# riffle-proto-0_1.net
KiCad netlist of a schematic drawn in EAGLE
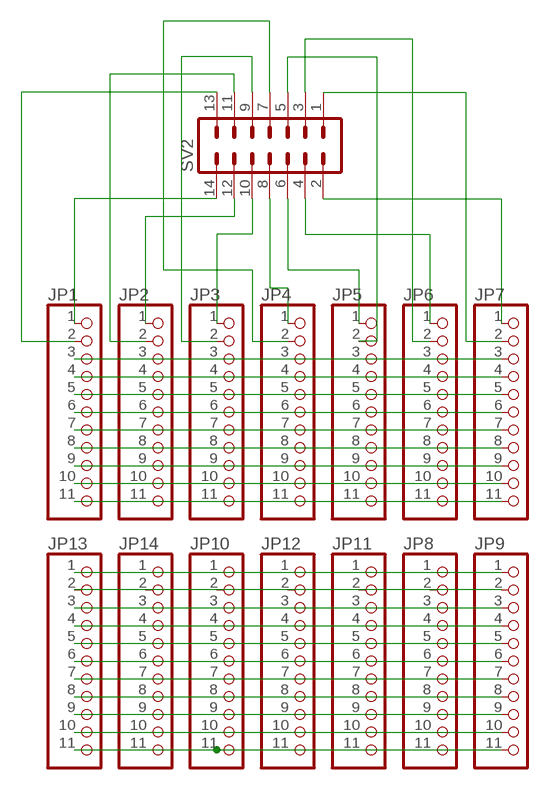
[diagram p0: schematic, sheet 1]

(export (version "E")
  (design (tool "Eeschema 10.0.6"))
  (components
    (comp (ref "JP1")
      (value "HEADER-1X1176MIL")
      (footprint "eagle-import:1X11_ROUND_76")
      (libsource (lib "eagle-import") (part "HEADER-1X1176MIL"))
    )
    (comp (ref "JP2")
      (value "HEADER-1X1176MIL")
      (footprint "eagle-import:1X11_ROUND_76")
      (libsource (lib "eagle-import") (part "HEADER-1X1176MIL"))
    )
    (comp (ref "JP3")
      (value "HEADER-1X1176MIL")
      (footprint "eagle-import:1X11_ROUND_76")
      (libsource (lib "eagle-import") (part "HEADER-1X1176MIL"))
    )
    (comp (ref "JP4")
      (value "HEADER-1X1176MIL")
      (footprint "eagle-import:1X11_ROUND_76")
      (libsource (lib "eagle-import") (part "HEADER-1X1176MIL"))
    )
    (comp (ref "JP5")
      (value "HEADER-1X1176MIL")
      (footprint "eagle-import:1X11_ROUND_76")
      (libsource (lib "eagle-import") (part "HEADER-1X1176MIL"))
    )
    (comp (ref "JP6")
      (value "HEADER-1X1176MIL")
      (footprint "eagle-import:1X11_ROUND_76")
      (libsource (lib "eagle-import") (part "HEADER-1X1176MIL"))
    )
    (comp (ref "JP7")
      (value "HEADER-1X1176MIL")
      (footprint "eagle-import:1X11_ROUND_76")
      (libsource (lib "eagle-import") (part "HEADER-1X1176MIL"))
    )
    (comp (ref "JP8")
      (value "HEADER-1X1176MIL")
      (footprint "eagle-import:1X11_ROUND_76")
      (libsource (lib "eagle-import") (part "HEADER-1X1176MIL"))
    )
    (comp (ref "JP9")
      (value "HEADER-1X1176MIL")
      (footprint "eagle-import:1X11_ROUND_76")
      (libsource (lib "eagle-import") (part "HEADER-1X1176MIL"))
    )
    (comp (ref "JP10")
      (value "HEADER-1X1176MIL")
      (footprint "eagle-import:1X11_ROUND_76")
      (libsource (lib "eagle-import") (part "HEADER-1X1176MIL"))
    )
    (comp (ref "JP11")
      (value "HEADER-1X1176MIL")
      (footprint "eagle-import:1X11_ROUND_76")
      (libsource (lib "eagle-import") (part "HEADER-1X1176MIL"))
    )
    (comp (ref "JP12")
      (value "HEADER-1X1176MIL")
      (footprint "eagle-import:1X11_ROUND_76")
      (libsource (lib "eagle-import") (part "HEADER-1X1176MIL"))
    )
    (comp (ref "JP13")
      (value "HEADER-1X1176MIL")
      (footprint "eagle-import:1X11_ROUND_76")
      (libsource (lib "eagle-import") (part "HEADER-1X1176MIL"))
    )
    (comp (ref "JP14")
      (value "HEADER-1X1176MIL")
      (footprint "eagle-import:1X11_ROUND_76")
      (libsource (lib "eagle-import") (part "HEADER-1X1176MIL"))
    )
    (comp (ref "SV2")
      (value "MA07-2")
      (footprint "eagle-import:MA07-2")
      (libsource (lib "eagle-import") (part "MA07-2"))
    )
  )
  (nets
    (net (code "1") (name "Net-(JP1-Pad1)") (class "Default")
      (node (ref "JP1") (pin "1") (pinfunction "1_1") (pintype "passive"))
      (node (ref "SV2") (pin "14") (pinfunction "14_14") (pintype "passive"))
    )
    (net (code "2") (name "Net-(JP1-Pad2)") (class "Default")
      (node (ref "JP1") (pin "2") (pinfunction "2_2") (pintype "passive"))
      (node (ref "SV2") (pin "13") (pinfunction "13_13") (pintype "passive"))
    )
    (net (code "3") (name "Net-(JP1-Pad3)") (class "Default")
      (node (ref "JP1") (pin "3") (pinfunction "3_3") (pintype "passive"))
      (node (ref "JP2") (pin "3") (pinfunction "3_3") (pintype "passive"))
      (node (ref "JP3") (pin "3") (pinfunction "3_3") (pintype "passive"))
      (node (ref "JP4") (pin "3") (pinfunction "3_3") (pintype "passive"))
      (node (ref "JP5") (pin "3") (pinfunction "3_3") (pintype "passive"))
      (node (ref "JP6") (pin "3") (pinfunction "3_3") (pintype "passive"))
      (node (ref "JP7") (pin "3") (pinfunction "3_3") (pintype "passive"))
    )
    (net (code "4") (name "Net-(JP1-Pad4)") (class "Default")
      (node (ref "JP1") (pin "4") (pinfunction "4_4") (pintype "passive"))
      (node (ref "JP2") (pin "4") (pinfunction "4_4") (pintype "passive"))
      (node (ref "JP3") (pin "4") (pinfunction "4_4") (pintype "passive"))
      (node (ref "JP4") (pin "4") (pinfunction "4_4") (pintype "passive"))
      (node (ref "JP5") (pin "4") (pinfunction "4_4") (pintype "passive"))
      (node (ref "JP6") (pin "4") (pinfunction "4_4") (pintype "passive"))
      (node (ref "JP7") (pin "4") (pinfunction "4_4") (pintype "passive"))
    )
    (net (code "5") (name "Net-(JP1-Pad5)") (class "Default")
      (node (ref "JP1") (pin "5") (pinfunction "5_5") (pintype "passive"))
      (node (ref "JP2") (pin "5") (pinfunction "5_5") (pintype "passive"))
      (node (ref "JP3") (pin "5") (pinfunction "5_5") (pintype "passive"))
      (node (ref "JP4") (pin "5") (pinfunction "5_5") (pintype "passive"))
      (node (ref "JP5") (pin "5") (pinfunction "5_5") (pintype "passive"))
      (node (ref "JP6") (pin "5") (pinfunction "5_5") (pintype "passive"))
      (node (ref "JP7") (pin "5") (pinfunction "5_5") (pintype "passive"))
    )
    (net (code "6") (name "Net-(JP1-Pad6)") (class "Default")
      (node (ref "JP1") (pin "6") (pinfunction "6_6") (pintype "passive"))
      (node (ref "JP2") (pin "6") (pinfunction "6_6") (pintype "passive"))
      (node (ref "JP3") (pin "6") (pinfunction "6_6") (pintype "passive"))
      (node (ref "JP4") (pin "6") (pinfunction "6_6") (pintype "passive"))
      (node (ref "JP5") (pin "6") (pinfunction "6_6") (pintype "passive"))
      (node (ref "JP6") (pin "6") (pinfunction "6_6") (pintype "passive"))
      (node (ref "JP7") (pin "6") (pinfunction "6_6") (pintype "passive"))
    )
    (net (code "7") (name "Net-(JP1-Pad7)") (class "Default")
      (node (ref "JP1") (pin "7") (pinfunction "7_7") (pintype "passive"))
      (node (ref "JP2") (pin "7") (pinfunction "7_7") (pintype "passive"))
      (node (ref "JP3") (pin "7") (pinfunction "7_7") (pintype "passive"))
      (node (ref "JP4") (pin "7") (pinfunction "7_7") (pintype "passive"))
      (node (ref "JP5") (pin "7") (pinfunction "7_7") (pintype "passive"))
      (node (ref "JP6") (pin "7") (pinfunction "7_7") (pintype "passive"))
      (node (ref "JP7") (pin "7") (pinfunction "7_7") (pintype "passive"))
    )
    (net (code "8") (name "Net-(JP1-Pad8)") (class "Default")
      (node (ref "JP1") (pin "8") (pinfunction "8_8") (pintype "passive"))
      (node (ref "JP2") (pin "8") (pinfunction "8_8") (pintype "passive"))
      (node (ref "JP3") (pin "8") (pinfunction "8_8") (pintype "passive"))
      (node (ref "JP4") (pin "8") (pinfunction "8_8") (pintype "passive"))
      (node (ref "JP5") (pin "8") (pinfunction "8_8") (pintype "passive"))
      (node (ref "JP6") (pin "8") (pinfunction "8_8") (pintype "passive"))
      (node (ref "JP7") (pin "8") (pinfunction "8_8") (pintype "passive"))
    )
    (net (code "9") (name "Net-(JP1-Pad9)") (class "Default")
      (node (ref "JP1") (pin "9") (pinfunction "9_9") (pintype "passive"))
      (node (ref "JP2") (pin "9") (pinfunction "9_9") (pintype "passive"))
      (node (ref "JP3") (pin "9") (pinfunction "9_9") (pintype "passive"))
      (node (ref "JP4") (pin "9") (pinfunction "9_9") (pintype "passive"))
      (node (ref "JP5") (pin "9") (pinfunction "9_9") (pintype "passive"))
      (node (ref "JP6") (pin "9") (pinfunction "9_9") (pintype "passive"))
      (node (ref "JP7") (pin "9") (pinfunction "9_9") (pintype "passive"))
    )
    (net (code "10") (name "Net-(JP1-Pad10)") (class "Default")
      (node (ref "JP1") (pin "10") (pinfunction "10_10") (pintype "passive"))
      (node (ref "JP2") (pin "10") (pinfunction "10_10") (pintype "passive"))
      (node (ref "JP3") (pin "10") (pinfunction "10_10") (pintype "passive"))
      (node (ref "JP4") (pin "10") (pinfunction "10_10") (pintype "passive"))
      (node (ref "JP5") (pin "10") (pinfunction "10_10") (pintype "passive"))
      (node (ref "JP6") (pin "10") (pinfunction "10_10") (pintype "passive"))
      (node (ref "JP7") (pin "10") (pinfunction "10_10") (pintype "passive"))
    )
    (net (code "11") (name "Net-(JP1-Pad11)") (class "Default")
      (node (ref "JP1") (pin "11") (pinfunction "11_11") (pintype "passive"))
      (node (ref "JP2") (pin "11") (pinfunction "11_11") (pintype "passive"))
      (node (ref "JP4") (pin "11") (pinfunction "11_11") (pintype "passive"))
      (node (ref "JP5") (pin "11") (pinfunction "11_11") (pintype "passive"))
      (node (ref "JP6") (pin "11") (pinfunction "11_11") (pintype "passive"))
      (node (ref "JP7") (pin "11") (pinfunction "11_11") (pintype "passive"))
    )
    (net (code "12") (name "Net-(JP2-Pad1)") (class "Default")
      (node (ref "JP2") (pin "1") (pinfunction "1_1") (pintype "passive"))
      (node (ref "SV2") (pin "12") (pinfunction "12_12") (pintype "passive"))
    )
    (net (code "13") (name "Net-(JP2-Pad2)") (class "Default")
      (node (ref "JP2") (pin "2") (pinfunction "2_2") (pintype "passive"))
      (node (ref "SV2") (pin "11") (pinfunction "11_11") (pintype "passive"))
    )
    (net (code "14") (name "Net-(JP3-Pad1)") (class "Default")
      (node (ref "JP3") (pin "1") (pinfunction "1_1") (pintype "passive"))
      (node (ref "SV2") (pin "10") (pinfunction "10_10") (pintype "passive"))
    )
    (net (code "15") (name "Net-(JP3-Pad2)") (class "Default")
      (node (ref "JP3") (pin "2") (pinfunction "2_2") (pintype "passive"))
      (node (ref "SV2") (pin "9") (pinfunction "9_9") (pintype "passive"))
    )
    (net (code "16") (name "Net-(JP4-Pad1)") (class "Default")
      (node (ref "JP4") (pin "1") (pinfunction "1_1") (pintype "passive"))
      (node (ref "SV2") (pin "8") (pinfunction "8_8") (pintype "passive"))
    )
    (net (code "17") (name "Net-(JP4-Pad2)") (class "Default")
      (node (ref "JP4") (pin "2") (pinfunction "2_2") (pintype "passive"))
      (node (ref "SV2") (pin "7") (pinfunction "7_7") (pintype "passive"))
    )
    (net (code "18") (name "Net-(JP5-Pad1)") (class "Default")
      (node (ref "JP5") (pin "1") (pinfunction "1_1") (pintype "passive"))
      (node (ref "SV2") (pin "6") (pinfunction "6_6") (pintype "passive"))
    )
    (net (code "19") (name "Net-(JP5-Pad2)") (class "Default")
      (node (ref "JP5") (pin "2") (pinfunction "2_2") (pintype "passive"))
      (node (ref "SV2") (pin "5") (pinfunction "5_5") (pintype "passive"))
    )
    (net (code "20") (name "Net-(JP6-Pad1)") (class "Default")
      (node (ref "JP6") (pin "1") (pinfunction "1_1") (pintype "passive"))
      (node (ref "SV2") (pin "4") (pinfunction "4_4") (pintype "passive"))
    )
    (net (code "21") (name "Net-(JP6-Pad2)") (class "Default")
      (node (ref "JP6") (pin "2") (pinfunction "2_2") (pintype "passive"))
      (node (ref "SV2") (pin "3") (pinfunction "3_3") (pintype "passive"))
    )
    (net (code "22") (name "Net-(JP7-Pad1)") (class "Default")
      (node (ref "JP7") (pin "1") (pinfunction "1_1") (pintype "passive"))
      (node (ref "SV2") (pin "2") (pinfunction "2_2") (pintype "passive"))
    )
    (net (code "23") (name "Net-(JP7-Pad2)") (class "Default")
      (node (ref "JP7") (pin "2") (pinfunction "2_2") (pintype "passive"))
      (node (ref "SV2") (pin "1") (pinfunction "1_1") (pintype "passive"))
    )
    (net (code "24") (name "Net-(JP10-Pad1)") (class "Default")
      (node (ref "JP10") (pin "1") (pinfunction "1_1") (pintype "passive"))
      (node (ref "JP11") (pin "1") (pinfunction "1_1") (pintype "passive"))
      (node (ref "JP12") (pin "1") (pinfunction "1_1") (pintype "passive"))
      (node (ref "JP13") (pin "1") (pinfunction "1_1") (pintype "passive"))
      (node (ref "JP14") (pin "1") (pinfunction "1_1") (pintype "passive"))
      (node (ref "JP8") (pin "1") (pinfunction "1_1") (pintype "passive"))
      (node (ref "JP9") (pin "1") (pinfunction "1_1") (pintype "passive"))
    )
    (net (code "25") (name "Net-(JP10-Pad2)") (class "Default")
      (node (ref "JP10") (pin "2") (pinfunction "2_2") (pintype "passive"))
      (node (ref "JP11") (pin "2") (pinfunction "2_2") (pintype "passive"))
      (node (ref "JP12") (pin "2") (pinfunction "2_2") (pintype "passive"))
      (node (ref "JP13") (pin "2") (pinfunction "2_2") (pintype "passive"))
      (node (ref "JP14") (pin "2") (pinfunction "2_2") (pintype "passive"))
      (node (ref "JP8") (pin "2") (pinfunction "2_2") (pintype "passive"))
      (node (ref "JP9") (pin "2") (pinfunction "2_2") (pintype "passive"))
    )
    (net (code "26") (name "Net-(JP10-Pad3)") (class "Default")
      (node (ref "JP10") (pin "3") (pinfunction "3_3") (pintype "passive"))
      (node (ref "JP11") (pin "3") (pinfunction "3_3") (pintype "passive"))
      (node (ref "JP12") (pin "3") (pinfunction "3_3") (pintype "passive"))
      (node (ref "JP13") (pin "3") (pinfunction "3_3") (pintype "passive"))
      (node (ref "JP14") (pin "3") (pinfunction "3_3") (pintype "passive"))
      (node (ref "JP8") (pin "3") (pinfunction "3_3") (pintype "passive"))
      (node (ref "JP9") (pin "3") (pinfunction "3_3") (pintype "passive"))
    )
    (net (code "27") (name "Net-(JP10-Pad4)") (class "Default")
      (node (ref "JP10") (pin "4") (pinfunction "4_4") (pintype "passive"))
      (node (ref "JP11") (pin "4") (pinfunction "4_4") (pintype "passive"))
      (node (ref "JP12") (pin "4") (pinfunction "4_4") (pintype "passive"))
      (node (ref "JP13") (pin "4") (pinfunction "4_4") (pintype "passive"))
      (node (ref "JP14") (pin "4") (pinfunction "4_4") (pintype "passive"))
      (node (ref "JP8") (pin "4") (pinfunction "4_4") (pintype "passive"))
      (node (ref "JP9") (pin "4") (pinfunction "4_4") (pintype "passive"))
    )
    (net (code "28") (name "Net-(JP10-Pad5)") (class "Default")
      (node (ref "JP10") (pin "5") (pinfunction "5_5") (pintype "passive"))
      (node (ref "JP11") (pin "5") (pinfunction "5_5") (pintype "passive"))
      (node (ref "JP12") (pin "5") (pinfunction "5_5") (pintype "passive"))
      (node (ref "JP13") (pin "5") (pinfunction "5_5") (pintype "passive"))
      (node (ref "JP14") (pin "5") (pinfunction "5_5") (pintype "passive"))
      (node (ref "JP8") (pin "5") (pinfunction "5_5") (pintype "passive"))
      (node (ref "JP9") (pin "5") (pinfunction "5_5") (pintype "passive"))
    )
    (net (code "29") (name "Net-(JP10-Pad6)") (class "Default")
      (node (ref "JP10") (pin "6") (pinfunction "6_6") (pintype "passive"))
      (node (ref "JP11") (pin "6") (pinfunction "6_6") (pintype "passive"))
      (node (ref "JP12") (pin "6") (pinfunction "6_6") (pintype "passive"))
      (node (ref "JP13") (pin "6") (pinfunction "6_6") (pintype "passive"))
      (node (ref "JP14") (pin "6") (pinfunction "6_6") (pintype "passive"))
      (node (ref "JP8") (pin "6") (pinfunction "6_6") (pintype "passive"))
      (node (ref "JP9") (pin "6") (pinfunction "6_6") (pintype "passive"))
    )
    (net (code "30") (name "Net-(JP10-Pad7)") (class "Default")
      (node (ref "JP10") (pin "7") (pinfunction "7_7") (pintype "passive"))
      (node (ref "JP11") (pin "7") (pinfunction "7_7") (pintype "passive"))
      (node (ref "JP12") (pin "7") (pinfunction "7_7") (pintype "passive"))
      (node (ref "JP13") (pin "7") (pinfunction "7_7") (pintype "passive"))
      (node (ref "JP14") (pin "7") (pinfunction "7_7") (pintype "passive"))
      (node (ref "JP8") (pin "7") (pinfunction "7_7") (pintype "passive"))
      (node (ref "JP9") (pin "7") (pinfunction "7_7") (pintype "passive"))
    )
    (net (code "31") (name "Net-(JP10-Pad8)") (class "Default")
      (node (ref "JP10") (pin "8") (pinfunction "8_8") (pintype "passive"))
      (node (ref "JP11") (pin "8") (pinfunction "8_8") (pintype "passive"))
      (node (ref "JP12") (pin "8") (pinfunction "8_8") (pintype "passive"))
      (node (ref "JP13") (pin "8") (pinfunction "8_8") (pintype "passive"))
      (node (ref "JP14") (pin "8") (pinfunction "8_8") (pintype "passive"))
      (node (ref "JP8") (pin "8") (pinfunction "8_8") (pintype "passive"))
      (node (ref "JP9") (pin "8") (pinfunction "8_8") (pintype "passive"))
    )
    (net (code "32") (name "Net-(JP10-Pad9)") (class "Default")
      (node (ref "JP10") (pin "9") (pinfunction "9_9") (pintype "passive"))
      (node (ref "JP11") (pin "9") (pinfunction "9_9") (pintype "passive"))
      (node (ref "JP12") (pin "9") (pinfunction "9_9") (pintype "passive"))
      (node (ref "JP13") (pin "9") (pinfunction "9_9") (pintype "passive"))
      (node (ref "JP14") (pin "9") (pinfunction "9_9") (pintype "passive"))
      (node (ref "JP8") (pin "9") (pinfunction "9_9") (pintype "passive"))
      (node (ref "JP9") (pin "9") (pinfunction "9_9") (pintype "passive"))
    )
    (net (code "33") (name "Net-(JP10-Pad10)") (class "Default")
      (node (ref "JP10") (pin "10") (pinfunction "10_10") (pintype "passive"))
      (node (ref "JP11") (pin "10") (pinfunction "10_10") (pintype "passive"))
      (node (ref "JP12") (pin "10") (pinfunction "10_10") (pintype "passive"))
      (node (ref "JP13") (pin "10") (pinfunction "10_10") (pintype "passive"))
      (node (ref "JP14") (pin "10") (pinfunction "10_10") (pintype "passive"))
      (node (ref "JP8") (pin "10") (pinfunction "10_10") (pintype "passive"))
      (node (ref "JP9") (pin "10") (pinfunction "10_10") (pintype "passive"))
    )
    (net (code "34") (name "Net-(JP10-Pad11)") (class "Default")
      (node (ref "JP10") (pin "11") (pinfunction "11_11") (pintype "passive"))
      (node (ref "JP11") (pin "11") (pinfunction "11_11") (pintype "passive"))
      (node (ref "JP12") (pin "11") (pinfunction "11_11") (pintype "passive"))
      (node (ref "JP13") (pin "11") (pinfunction "11_11") (pintype "passive"))
      (node (ref "JP14") (pin "11") (pinfunction "11_11") (pintype "passive"))
      (node (ref "JP8") (pin "11") (pinfunction "11_11") (pintype "passive"))
      (node (ref "JP9") (pin "11") (pinfunction "11_11") (pintype "passive"))
    )
    (net (code "35") (name "unconnected-(JP3-Pad11)") (class "Default")
      (node (ref "JP3") (pin "11") (pinfunction "11_11") (pintype "passive"))
    )
  )
)
